# 2x2AND_OR_1.net
KiCad netlist of a schematic drawn in EAGLE
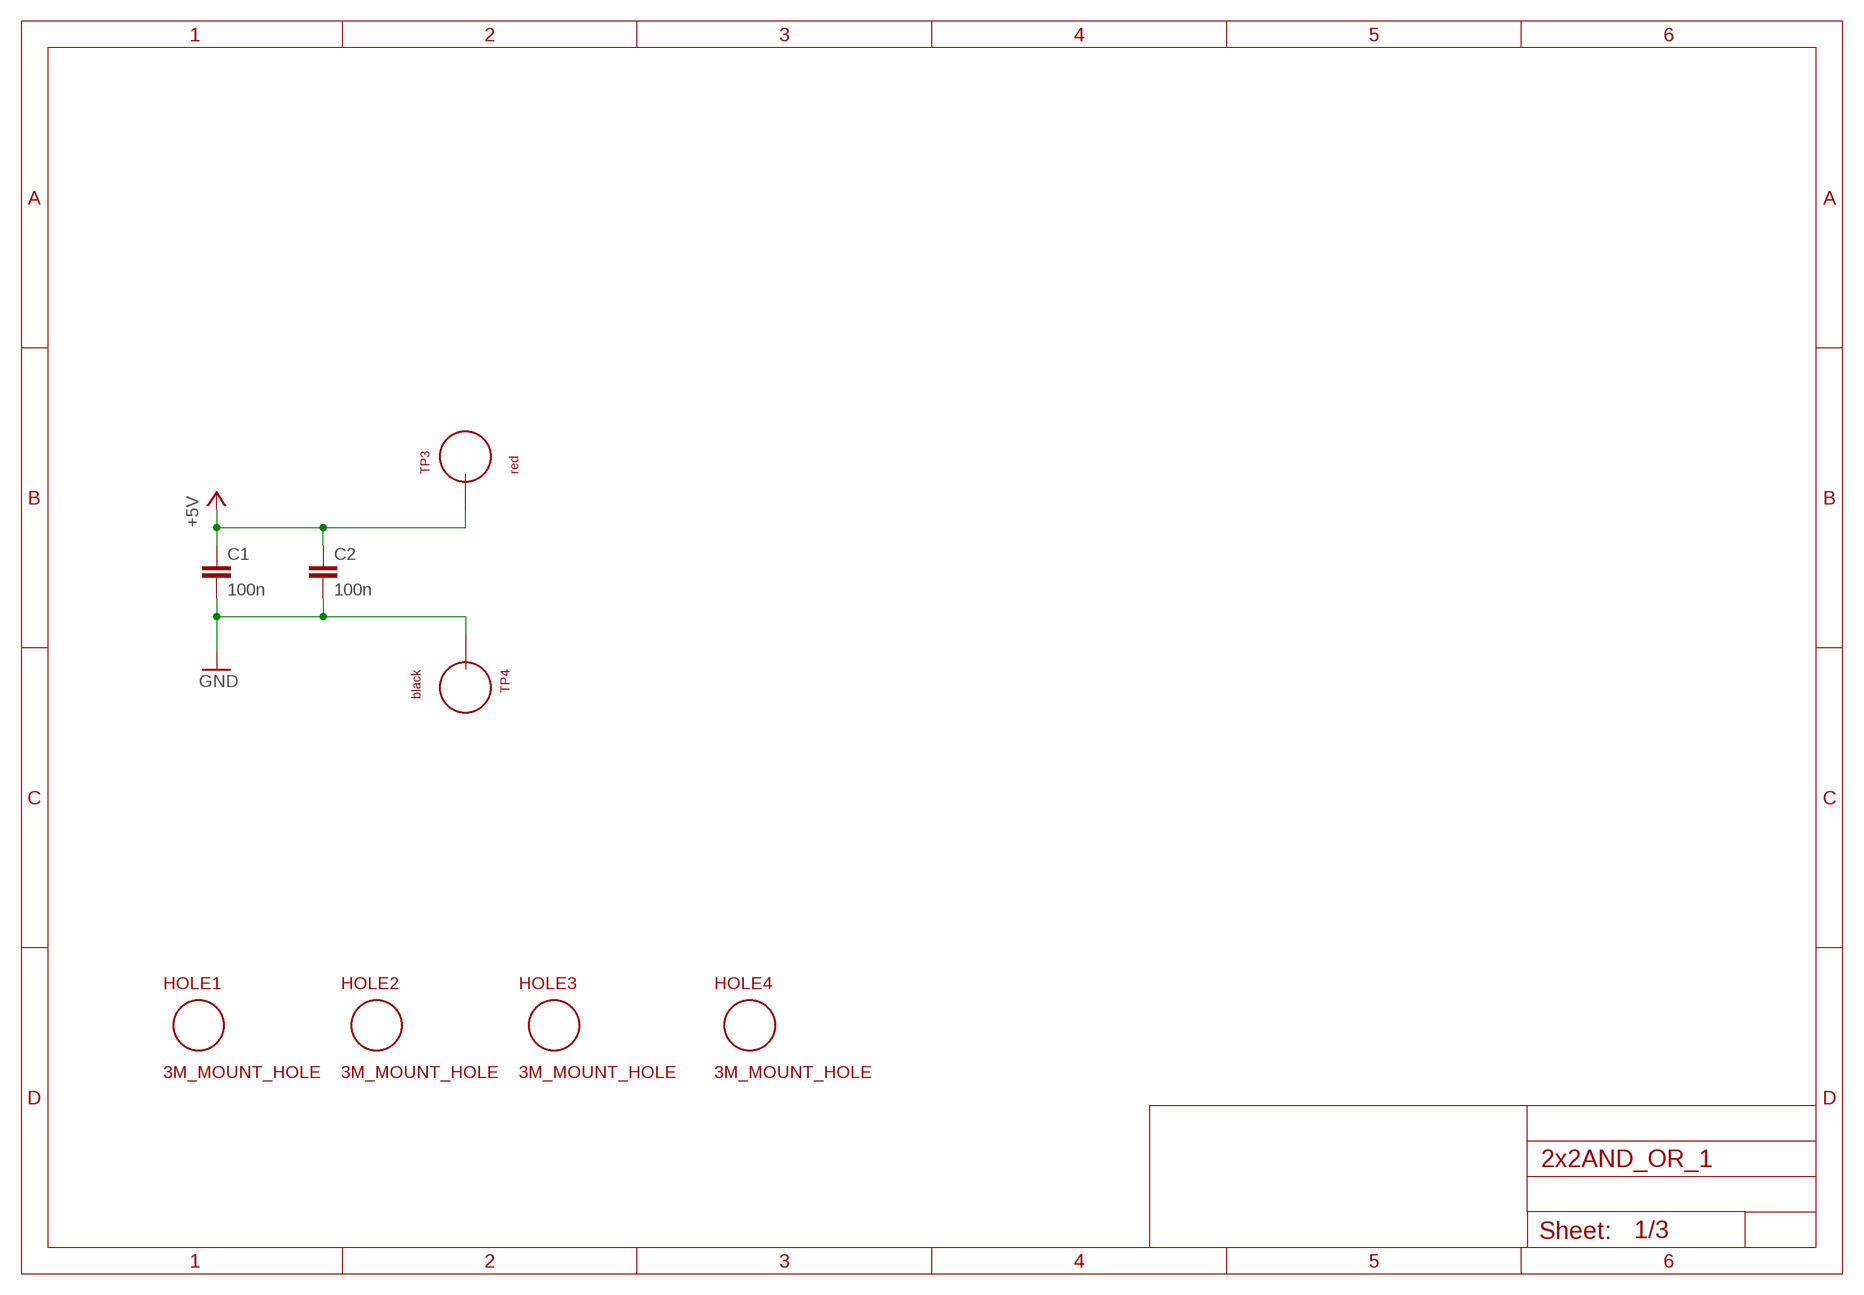
[diagram p0: schematic, sheet 1]
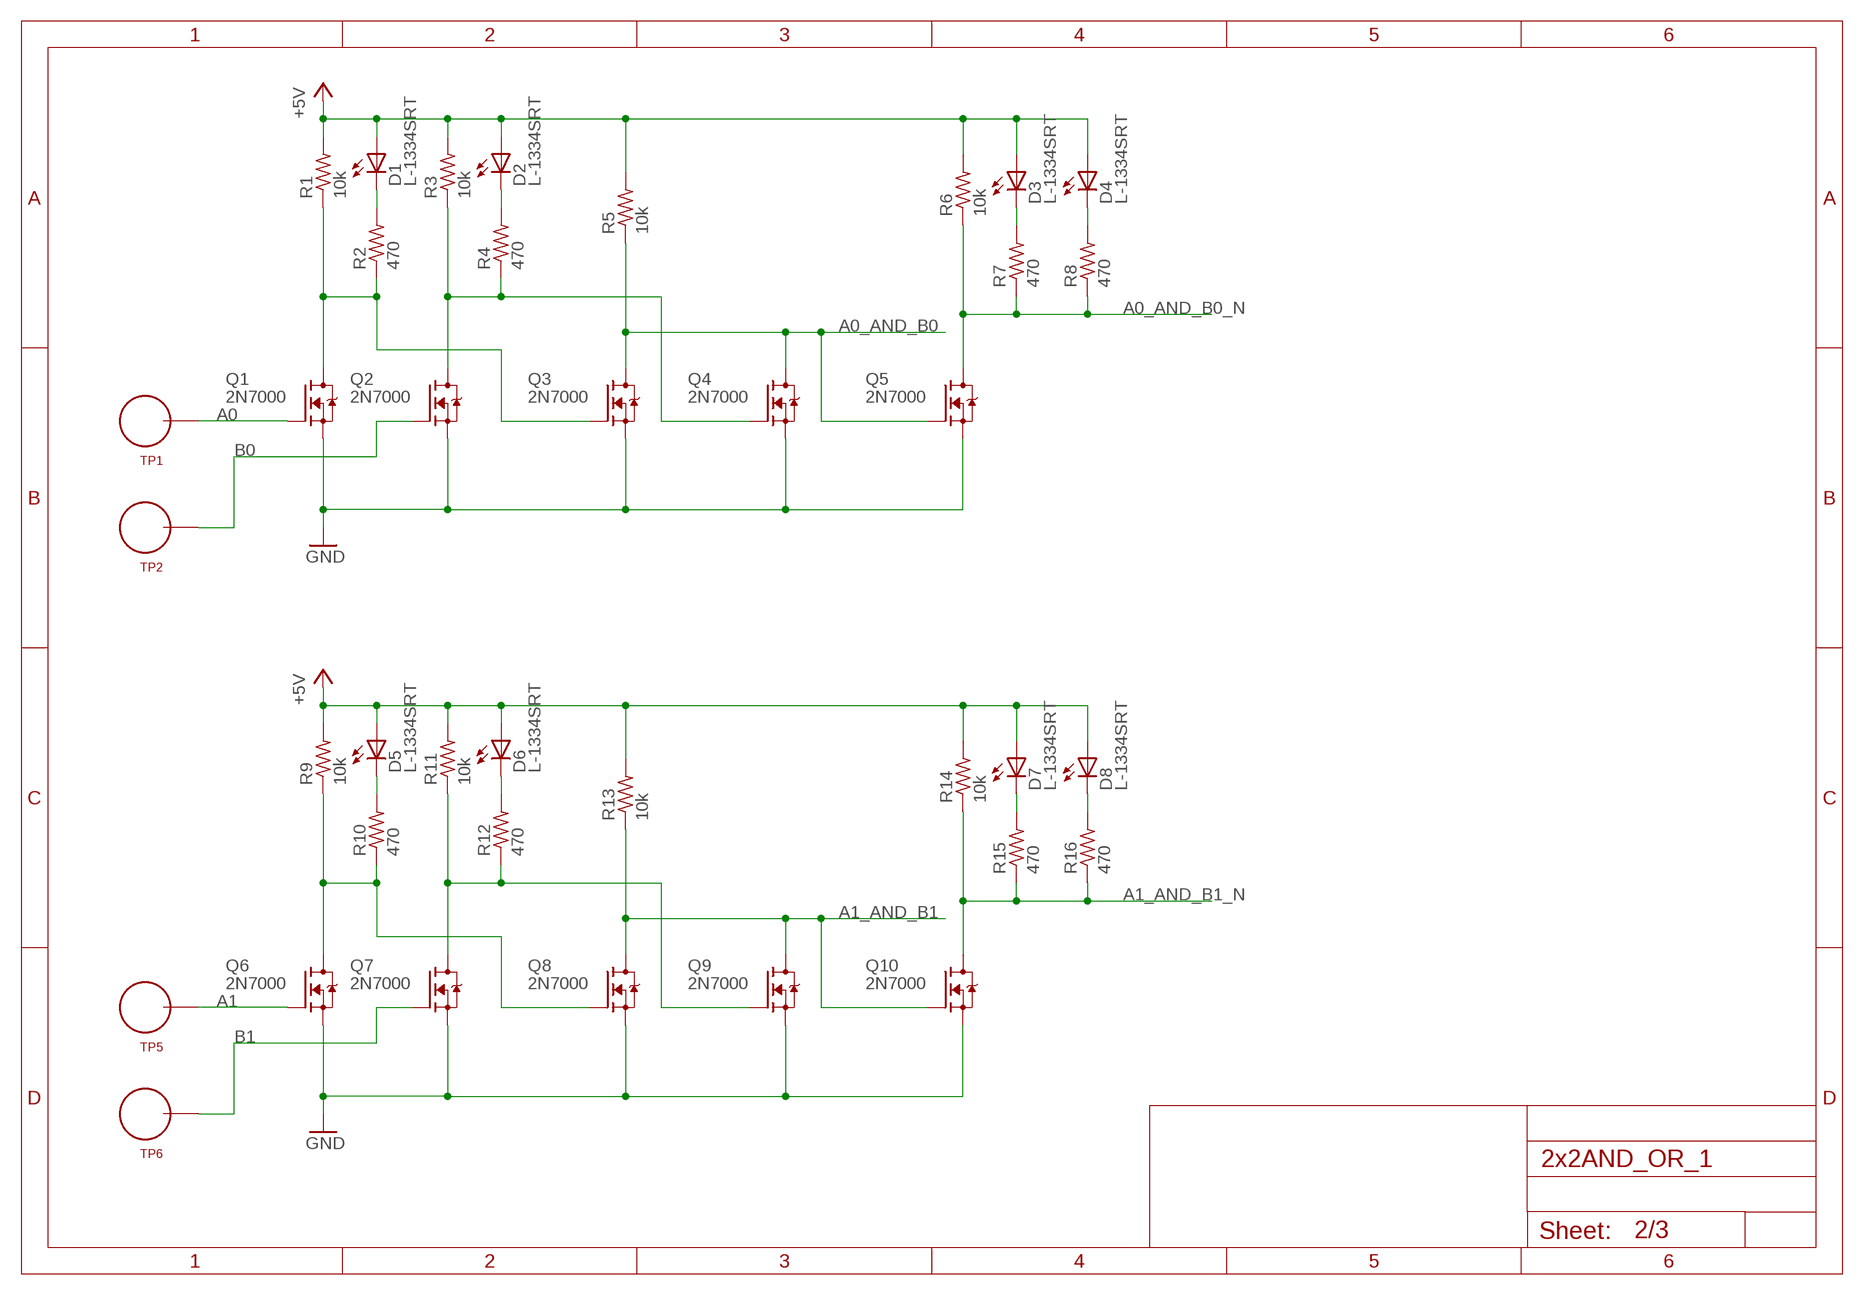
[diagram p1: schematic, sheet 2]
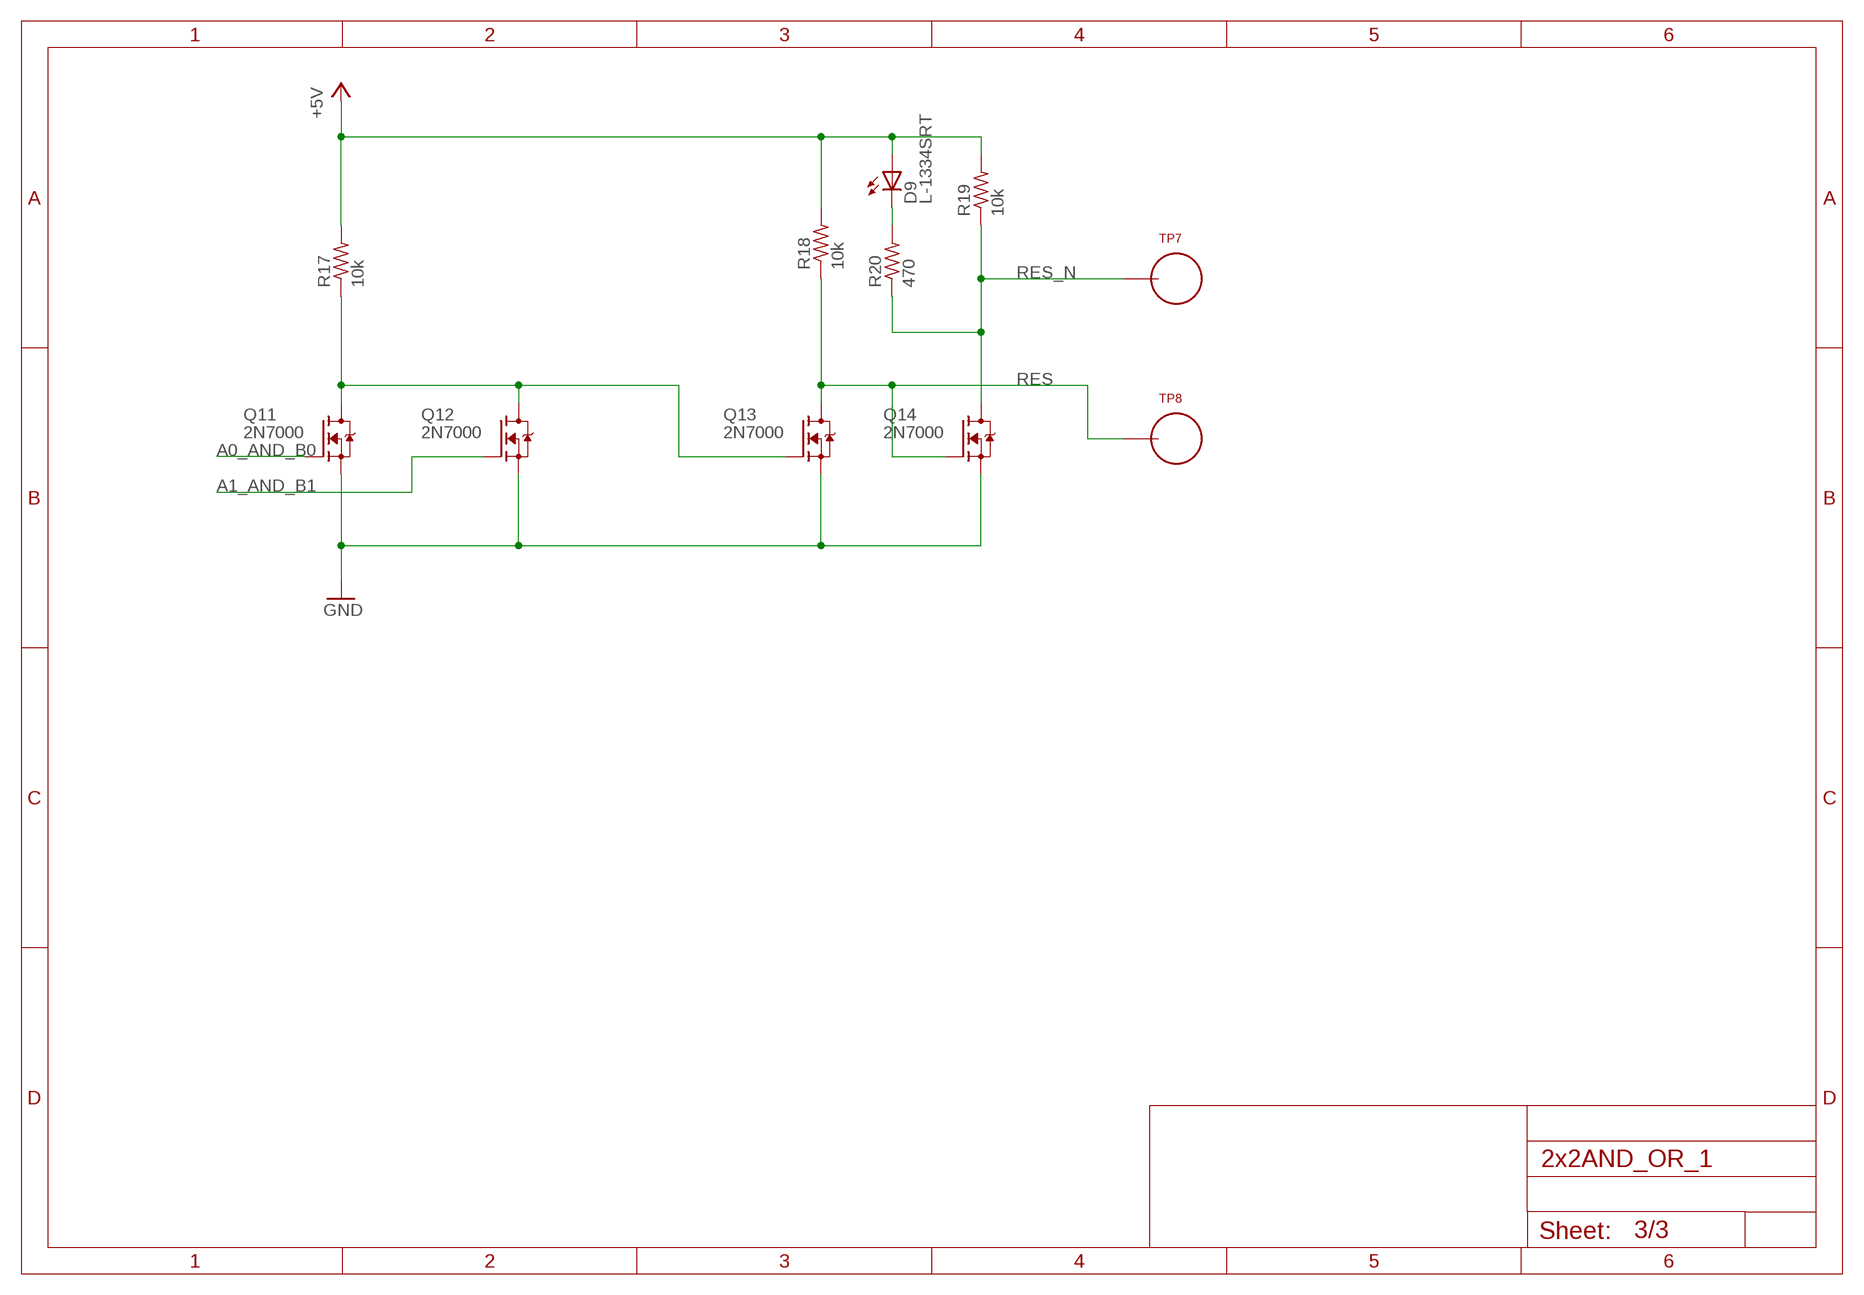
[diagram p2: schematic, sheet 3]

(export (version "E")
  (design (tool "Eeschema 10.0.6"))
  (components
    (comp (ref "D1")
      (value "L-1334SRT")
      (footprint "eagle-import:LED3MM")
      (libsource (lib "eagle-import") (part "L-1334SRT"))
    )
    (comp (ref "D2")
      (value "L-1334SRT")
      (footprint "eagle-import:LED3MM")
      (libsource (lib "eagle-import") (part "L-1334SRT"))
    )
    (comp (ref "D3")
      (value "L-1334SRT")
      (footprint "eagle-import:LED3MM")
      (libsource (lib "eagle-import") (part "L-1334SRT"))
    )
    (comp (ref "D4")
      (value "L-1334SRT")
      (footprint "eagle-import:LED3MM")
      (libsource (lib "eagle-import") (part "L-1334SRT"))
    )
    (comp (ref "D5")
      (value "L-1334SRT")
      (footprint "eagle-import:LED3MM")
      (libsource (lib "eagle-import") (part "L-1334SRT"))
    )
    (comp (ref "D6")
      (value "L-1334SRT")
      (footprint "eagle-import:LED3MM")
      (libsource (lib "eagle-import") (part "L-1334SRT"))
    )
    (comp (ref "D7")
      (value "L-1334SRT")
      (footprint "eagle-import:LED3MM")
      (libsource (lib "eagle-import") (part "L-1334SRT"))
    )
    (comp (ref "D8")
      (value "L-1334SRT")
      (footprint "eagle-import:LED3MM")
      (libsource (lib "eagle-import") (part "L-1334SRT"))
    )
    (comp (ref "Q1")
      (value "2N7000")
      (footprint "eagle-import:TO92-DGS")
      (libsource (lib "eagle-import") (part "2N7000"))
    )
    (comp (ref "Q2")
      (value "2N7000")
      (footprint "eagle-import:TO92-DGS")
      (libsource (lib "eagle-import") (part "2N7000"))
    )
    (comp (ref "Q3")
      (value "2N7000")
      (footprint "eagle-import:TO92-DGS")
      (libsource (lib "eagle-import") (part "2N7000"))
    )
    (comp (ref "Q4")
      (value "2N7000")
      (footprint "eagle-import:TO92-DGS")
      (libsource (lib "eagle-import") (part "2N7000"))
    )
    (comp (ref "Q5")
      (value "2N7000")
      (footprint "eagle-import:TO92-DGS")
      (libsource (lib "eagle-import") (part "2N7000"))
    )
    (comp (ref "Q6")
      (value "2N7000")
      (footprint "eagle-import:TO92-DGS")
      (libsource (lib "eagle-import") (part "2N7000"))
    )
    (comp (ref "Q7")
      (value "2N7000")
      (footprint "eagle-import:TO92-DGS")
      (libsource (lib "eagle-import") (part "2N7000"))
    )
    (comp (ref "Q8")
      (value "2N7000")
      (footprint "eagle-import:TO92-DGS")
      (libsource (lib "eagle-import") (part "2N7000"))
    )
    (comp (ref "Q9")
      (value "2N7000")
      (footprint "eagle-import:TO92-DGS")
      (libsource (lib "eagle-import") (part "2N7000"))
    )
    (comp (ref "Q10")
      (value "2N7000")
      (footprint "eagle-import:TO92-DGS")
      (libsource (lib "eagle-import") (part "2N7000"))
    )
    (comp (ref "R1")
      (value "10k")
      (footprint "eagle-import:R_P2INCH")
      (libsource (lib "eagle-import") (part "R_P2INCH"))
    )
    (comp (ref "R2")
      (value "470")
      (footprint "eagle-import:R_P2INCH")
      (libsource (lib "eagle-import") (part "R_P2INCH"))
    )
    (comp (ref "R3")
      (value "10k")
      (footprint "eagle-import:R_P2INCH")
      (libsource (lib "eagle-import") (part "R_P2INCH"))
    )
    (comp (ref "R4")
      (value "470")
      (footprint "eagle-import:R_P2INCH")
      (libsource (lib "eagle-import") (part "R_P2INCH"))
    )
    (comp (ref "R5")
      (value "10k")
      (footprint "eagle-import:R_P2INCH")
      (libsource (lib "eagle-import") (part "R_P2INCH"))
    )
    (comp (ref "R6")
      (value "10k")
      (footprint "eagle-import:R_P2INCH")
      (libsource (lib "eagle-import") (part "R_P2INCH"))
    )
    (comp (ref "R7")
      (value "470")
      (footprint "eagle-import:R_P2INCH")
      (libsource (lib "eagle-import") (part "R_P2INCH"))
    )
    (comp (ref "R8")
      (value "470")
      (footprint "eagle-import:R_P2INCH")
      (libsource (lib "eagle-import") (part "R_P2INCH"))
    )
    (comp (ref "R9")
      (value "10k")
      (footprint "eagle-import:R_P2INCH")
      (libsource (lib "eagle-import") (part "R_P2INCH"))
    )
    (comp (ref "R10")
      (value "470")
      (footprint "eagle-import:R_P2INCH")
      (libsource (lib "eagle-import") (part "R_P2INCH"))
    )
    (comp (ref "R11")
      (value "10k")
      (footprint "eagle-import:R_P2INCH")
      (libsource (lib "eagle-import") (part "R_P2INCH"))
    )
    (comp (ref "R12")
      (value "470")
      (footprint "eagle-import:R_P2INCH")
      (libsource (lib "eagle-import") (part "R_P2INCH"))
    )
    (comp (ref "R13")
      (value "10k")
      (footprint "eagle-import:R_P2INCH")
      (libsource (lib "eagle-import") (part "R_P2INCH"))
    )
    (comp (ref "R14")
      (value "10k")
      (footprint "eagle-import:R_P2INCH")
      (libsource (lib "eagle-import") (part "R_P2INCH"))
    )
    (comp (ref "R15")
      (value "470")
      (footprint "eagle-import:R_P2INCH")
      (libsource (lib "eagle-import") (part "R_P2INCH"))
    )
    (comp (ref "R16")
      (value "470")
      (footprint "eagle-import:R_P2INCH")
      (libsource (lib "eagle-import") (part "R_P2INCH"))
    )
    (comp (ref "TP1")
      (value "TEST_LOOP")
      (footprint "eagle-import:TEST_LOOP")
      (libsource (lib "eagle-import") (part "TEST_LOOP"))
    )
    (comp (ref "TP2")
      (value "TEST_LOOP")
      (footprint "eagle-import:TEST_LOOP")
      (libsource (lib "eagle-import") (part "TEST_LOOP"))
    )
    (comp (ref "TP5")
      (value "TEST_LOOP")
      (footprint "eagle-import:TEST_LOOP")
      (libsource (lib "eagle-import") (part "TEST_LOOP"))
    )
    (comp (ref "TP6")
      (value "TEST_LOOP")
      (footprint "eagle-import:TEST_LOOP")
      (libsource (lib "eagle-import") (part "TEST_LOOP"))
    )
    (comp (ref "C1")
      (value "100n")
      (footprint "eagle-import:CAP_P2INCH")
      (libsource (lib "eagle-import") (part "C_P2INCH"))
    )
    (comp (ref "C2")
      (value "100n")
      (footprint "eagle-import:CAP_P2INCH")
      (libsource (lib "eagle-import") (part "C_P2INCH"))
    )
    (comp (ref "HOLE1")
      (value "3M_MOUNT_HOLE")
      (footprint "eagle-import:3M_HOLE")
      (libsource (lib "eagle-import") (part "3M_MOUNT_HOLE"))
    )
    (comp (ref "HOLE2")
      (value "3M_MOUNT_HOLE")
      (footprint "eagle-import:3M_HOLE")
      (libsource (lib "eagle-import") (part "3M_MOUNT_HOLE"))
    )
    (comp (ref "HOLE3")
      (value "3M_MOUNT_HOLE")
      (footprint "eagle-import:3M_HOLE")
      (libsource (lib "eagle-import") (part "3M_MOUNT_HOLE"))
    )
    (comp (ref "HOLE4")
      (value "3M_MOUNT_HOLE")
      (footprint "eagle-import:3M_HOLE")
      (libsource (lib "eagle-import") (part "3M_MOUNT_HOLE"))
    )
    (comp (ref "TP3")
      (value "red")
      (footprint "eagle-import:TEST_LOOP")
      (libsource (lib "eagle-import") (part "TEST_LOOP"))
    )
    (comp (ref "TP4")
      (value "black")
      (footprint "eagle-import:TEST_LOOP")
      (libsource (lib "eagle-import") (part "TEST_LOOP"))
    )
    (comp (ref "D9")
      (value "L-1334SRT")
      (footprint "eagle-import:LED3MM")
      (libsource (lib "eagle-import") (part "L-1334SRT"))
    )
    (comp (ref "Q11")
      (value "2N7000")
      (footprint "eagle-import:TO92-DGS")
      (libsource (lib "eagle-import") (part "2N7000"))
    )
    (comp (ref "Q12")
      (value "2N7000")
      (footprint "eagle-import:TO92-DGS")
      (libsource (lib "eagle-import") (part "2N7000"))
    )
    (comp (ref "Q13")
      (value "2N7000")
      (footprint "eagle-import:TO92-DGS")
      (libsource (lib "eagle-import") (part "2N7000"))
    )
    (comp (ref "Q14")
      (value "2N7000")
      (footprint "eagle-import:TO92-DGS")
      (libsource (lib "eagle-import") (part "2N7000"))
    )
    (comp (ref "R17")
      (value "10k")
      (footprint "eagle-import:R_P2INCH")
      (libsource (lib "eagle-import") (part "R_P2INCH"))
    )
    (comp (ref "R18")
      (value "10k")
      (footprint "eagle-import:R_P2INCH")
      (libsource (lib "eagle-import") (part "R_P2INCH"))
    )
    (comp (ref "R19")
      (value "10k")
      (footprint "eagle-import:R_P2INCH")
      (libsource (lib "eagle-import") (part "R_P2INCH"))
    )
    (comp (ref "R20")
      (value "470")
      (footprint "eagle-import:R_P2INCH")
      (libsource (lib "eagle-import") (part "R_P2INCH"))
    )
    (comp (ref "TP7")
      (value "TEST_LOOP")
      (footprint "eagle-import:TEST_LOOP")
      (libsource (lib "eagle-import") (part "TEST_LOOP"))
    )
    (comp (ref "TP8")
      (value "TEST_LOOP")
      (footprint "eagle-import:TEST_LOOP")
      (libsource (lib "eagle-import") (part "TEST_LOOP"))
    )
  )
  (nets
    (net (code "1") (name "+5V") (class "Default")
      (node (ref "C1") (pin "1") (pinfunction "1_1") (pintype "passive"))
      (node (ref "C2") (pin "1") (pinfunction "1_1") (pintype "passive"))
      (node (ref "D1") (pin "A") (pinfunction "A_A") (pintype "passive"))
      (node (ref "D2") (pin "A") (pinfunction "A_A") (pintype "passive"))
      (node (ref "D3") (pin "A") (pinfunction "A_A") (pintype "passive"))
      (node (ref "D4") (pin "A") (pinfunction "A_A") (pintype "passive"))
      (node (ref "D5") (pin "A") (pinfunction "A_A") (pintype "passive"))
      (node (ref "D6") (pin "A") (pinfunction "A_A") (pintype "passive"))
      (node (ref "D7") (pin "A") (pinfunction "A_A") (pintype "passive"))
      (node (ref "D8") (pin "A") (pinfunction "A_A") (pintype "passive"))
      (node (ref "D9") (pin "A") (pinfunction "A_A") (pintype "passive"))
      (node (ref "R1") (pin "2") (pinfunction "2_2") (pintype "passive"))
      (node (ref "R11") (pin "2") (pinfunction "2_2") (pintype "passive"))
      (node (ref "R13") (pin "2") (pinfunction "2_2") (pintype "passive"))
      (node (ref "R14") (pin "2") (pinfunction "2_2") (pintype "passive"))
      (node (ref "R17") (pin "2") (pinfunction "2_2") (pintype "passive"))
      (node (ref "R18") (pin "2") (pinfunction "2_2") (pintype "passive"))
      (node (ref "R19") (pin "2") (pinfunction "2_2") (pintype "passive"))
      (node (ref "R3") (pin "2") (pinfunction "2_2") (pintype "passive"))
      (node (ref "R5") (pin "2") (pinfunction "2_2") (pintype "passive"))
      (node (ref "R6") (pin "2") (pinfunction "2_2") (pintype "passive"))
      (node (ref "R9") (pin "2") (pinfunction "2_2") (pintype "passive"))
      (node (ref "TP3") (pin "P$1") (pinfunction "P$1_P$1") (pintype "bidirectional"))
    )
    (net (code "2") (name "A0") (class "Default")
      (node (ref "Q1") (pin "G") (pinfunction "G_G") (pintype "passive"))
      (node (ref "TP1") (pin "P$1") (pinfunction "P$1_P$1") (pintype "bidirectional"))
    )
    (net (code "3") (name "A0_AND_B0") (class "Default")
      (node (ref "Q11") (pin "G") (pinfunction "G_G") (pintype "passive"))
      (node (ref "Q3") (pin "D") (pinfunction "D_D") (pintype "passive"))
      (node (ref "Q4") (pin "D") (pinfunction "D_D") (pintype "passive"))
      (node (ref "Q5") (pin "G") (pinfunction "G_G") (pintype "passive"))
      (node (ref "R5") (pin "1") (pinfunction "1_1") (pintype "passive"))
    )
    (net (code "4") (name "A0_AND_B0_N") (class "Default")
      (node (ref "Q5") (pin "D") (pinfunction "D_D") (pintype "passive"))
      (node (ref "R6") (pin "1") (pinfunction "1_1") (pintype "passive"))
      (node (ref "R7") (pin "1") (pinfunction "1_1") (pintype "passive"))
      (node (ref "R8") (pin "1") (pinfunction "1_1") (pintype "passive"))
    )
    (net (code "5") (name "A1") (class "Default")
      (node (ref "Q6") (pin "G") (pinfunction "G_G") (pintype "passive"))
      (node (ref "TP5") (pin "P$1") (pinfunction "P$1_P$1") (pintype "bidirectional"))
    )
    (net (code "6") (name "A1_AND_B1") (class "Default")
      (node (ref "Q10") (pin "G") (pinfunction "G_G") (pintype "passive"))
      (node (ref "Q12") (pin "G") (pinfunction "G_G") (pintype "passive"))
      (node (ref "Q8") (pin "D") (pinfunction "D_D") (pintype "passive"))
      (node (ref "Q9") (pin "D") (pinfunction "D_D") (pintype "passive"))
      (node (ref "R13") (pin "1") (pinfunction "1_1") (pintype "passive"))
    )
    (net (code "7") (name "A1_AND_B1_N") (class "Default")
      (node (ref "Q10") (pin "D") (pinfunction "D_D") (pintype "passive"))
      (node (ref "R14") (pin "1") (pinfunction "1_1") (pintype "passive"))
      (node (ref "R15") (pin "1") (pinfunction "1_1") (pintype "passive"))
      (node (ref "R16") (pin "1") (pinfunction "1_1") (pintype "passive"))
    )
    (net (code "8") (name "B0") (class "Default")
      (node (ref "Q2") (pin "G") (pinfunction "G_G") (pintype "passive"))
      (node (ref "TP2") (pin "P$1") (pinfunction "P$1_P$1") (pintype "bidirectional"))
    )
    (net (code "9") (name "B1") (class "Default")
      (node (ref "Q7") (pin "G") (pinfunction "G_G") (pintype "passive"))
      (node (ref "TP6") (pin "P$1") (pinfunction "P$1_P$1") (pintype "bidirectional"))
    )
    (net (code "10") (name "GND") (class "Default")
      (node (ref "C1") (pin "2") (pinfunction "2_2") (pintype "passive"))
      (node (ref "C2") (pin "2") (pinfunction "2_2") (pintype "passive"))
      (node (ref "Q1") (pin "S") (pinfunction "S_S") (pintype "passive"))
      (node (ref "Q10") (pin "S") (pinfunction "S_S") (pintype "passive"))
      (node (ref "Q11") (pin "S") (pinfunction "S_S") (pintype "passive"))
      (node (ref "Q12") (pin "S") (pinfunction "S_S") (pintype "passive"))
      (node (ref "Q13") (pin "S") (pinfunction "S_S") (pintype "passive"))
      (node (ref "Q14") (pin "S") (pinfunction "S_S") (pintype "passive"))
      (node (ref "Q2") (pin "S") (pinfunction "S_S") (pintype "passive"))
      (node (ref "Q3") (pin "S") (pinfunction "S_S") (pintype "passive"))
      (node (ref "Q4") (pin "S") (pinfunction "S_S") (pintype "passive"))
      (node (ref "Q5") (pin "S") (pinfunction "S_S") (pintype "passive"))
      (node (ref "Q6") (pin "S") (pinfunction "S_S") (pintype "passive"))
      (node (ref "Q7") (pin "S") (pinfunction "S_S") (pintype "passive"))
      (node (ref "Q8") (pin "S") (pinfunction "S_S") (pintype "passive"))
      (node (ref "Q9") (pin "S") (pinfunction "S_S") (pintype "passive"))
      (node (ref "TP4") (pin "P$1") (pinfunction "P$1_P$1") (pintype "bidirectional"))
    )
    (net (code "11") (name "Net-(D1-C)") (class "Default")
      (node (ref "D1") (pin "K") (pinfunction "C_K") (pintype "passive"))
      (node (ref "R2") (pin "2") (pinfunction "2_2") (pintype "passive"))
    )
    (net (code "12") (name "Net-(D2-C)") (class "Default")
      (node (ref "D2") (pin "K") (pinfunction "C_K") (pintype "passive"))
      (node (ref "R4") (pin "2") (pinfunction "2_2") (pintype "passive"))
    )
    (net (code "13") (name "Net-(D3-C)") (class "Default")
      (node (ref "D3") (pin "K") (pinfunction "C_K") (pintype "passive"))
      (node (ref "R7") (pin "2") (pinfunction "2_2") (pintype "passive"))
    )
    (net (code "14") (name "Net-(D4-C)") (class "Default")
      (node (ref "D4") (pin "K") (pinfunction "C_K") (pintype "passive"))
      (node (ref "R8") (pin "2") (pinfunction "2_2") (pintype "passive"))
    )
    (net (code "15") (name "Net-(D5-C)") (class "Default")
      (node (ref "D5") (pin "K") (pinfunction "C_K") (pintype "passive"))
      (node (ref "R10") (pin "2") (pinfunction "2_2") (pintype "passive"))
    )
    (net (code "16") (name "Net-(D6-C)") (class "Default")
      (node (ref "D6") (pin "K") (pinfunction "C_K") (pintype "passive"))
      (node (ref "R12") (pin "2") (pinfunction "2_2") (pintype "passive"))
    )
    (net (code "17") (name "Net-(D7-C)") (class "Default")
      (node (ref "D7") (pin "K") (pinfunction "C_K") (pintype "passive"))
      (node (ref "R15") (pin "2") (pinfunction "2_2") (pintype "passive"))
    )
    (net (code "18") (name "Net-(D8-C)") (class "Default")
      (node (ref "D8") (pin "K") (pinfunction "C_K") (pintype "passive"))
      (node (ref "R16") (pin "2") (pinfunction "2_2") (pintype "passive"))
    )
    (net (code "19") (name "Net-(D9-C)") (class "Default")
      (node (ref "D9") (pin "K") (pinfunction "C_K") (pintype "passive"))
      (node (ref "R20") (pin "2") (pinfunction "2_2") (pintype "passive"))
    )
    (net (code "20") (name "Net-(Q1-PadD)") (class "Default")
      (node (ref "Q1") (pin "D") (pinfunction "D_D") (pintype "passive"))
      (node (ref "Q3") (pin "G") (pinfunction "G_G") (pintype "passive"))
      (node (ref "R1") (pin "1") (pinfunction "1_1") (pintype "passive"))
      (node (ref "R2") (pin "1") (pinfunction "1_1") (pintype "passive"))
    )
    (net (code "21") (name "Net-(Q2-PadD)") (class "Default")
      (node (ref "Q2") (pin "D") (pinfunction "D_D") (pintype "passive"))
      (node (ref "Q4") (pin "G") (pinfunction "G_G") (pintype "passive"))
      (node (ref "R3") (pin "1") (pinfunction "1_1") (pintype "passive"))
      (node (ref "R4") (pin "1") (pinfunction "1_1") (pintype "passive"))
    )
    (net (code "22") (name "Net-(Q6-PadD)") (class "Default")
      (node (ref "Q6") (pin "D") (pinfunction "D_D") (pintype "passive"))
      (node (ref "Q8") (pin "G") (pinfunction "G_G") (pintype "passive"))
      (node (ref "R10") (pin "1") (pinfunction "1_1") (pintype "passive"))
      (node (ref "R9") (pin "1") (pinfunction "1_1") (pintype "passive"))
    )
    (net (code "23") (name "Net-(Q7-PadD)") (class "Default")
      (node (ref "Q7") (pin "D") (pinfunction "D_D") (pintype "passive"))
      (node (ref "Q9") (pin "G") (pinfunction "G_G") (pintype "passive"))
      (node (ref "R11") (pin "1") (pinfunction "1_1") (pintype "passive"))
      (node (ref "R12") (pin "1") (pinfunction "1_1") (pintype "passive"))
    )
    (net (code "24") (name "Net-(Q11-PadD)") (class "Default")
      (node (ref "Q11") (pin "D") (pinfunction "D_D") (pintype "passive"))
      (node (ref "Q12") (pin "D") (pinfunction "D_D") (pintype "passive"))
      (node (ref "Q13") (pin "G") (pinfunction "G_G") (pintype "passive"))
      (node (ref "R17") (pin "1") (pinfunction "1_1") (pintype "passive"))
    )
    (net (code "25") (name "RES") (class "Default")
      (node (ref "Q13") (pin "D") (pinfunction "D_D") (pintype "passive"))
      (node (ref "Q14") (pin "G") (pinfunction "G_G") (pintype "passive"))
      (node (ref "R18") (pin "1") (pinfunction "1_1") (pintype "passive"))
      (node (ref "TP8") (pin "P$1") (pinfunction "P$1_P$1") (pintype "bidirectional"))
    )
    (net (code "26") (name "RES_N") (class "Default")
      (node (ref "Q14") (pin "D") (pinfunction "D_D") (pintype "passive"))
      (node (ref "R19") (pin "1") (pinfunction "1_1") (pintype "passive"))
      (node (ref "R20") (pin "1") (pinfunction "1_1") (pintype "passive"))
      (node (ref "TP7") (pin "P$1") (pinfunction "P$1_P$1") (pintype "bidirectional"))
    )
  )
)
